# Front_left_lamp_v1.net
KiCad netlist of a schematic drawn in EAGLE
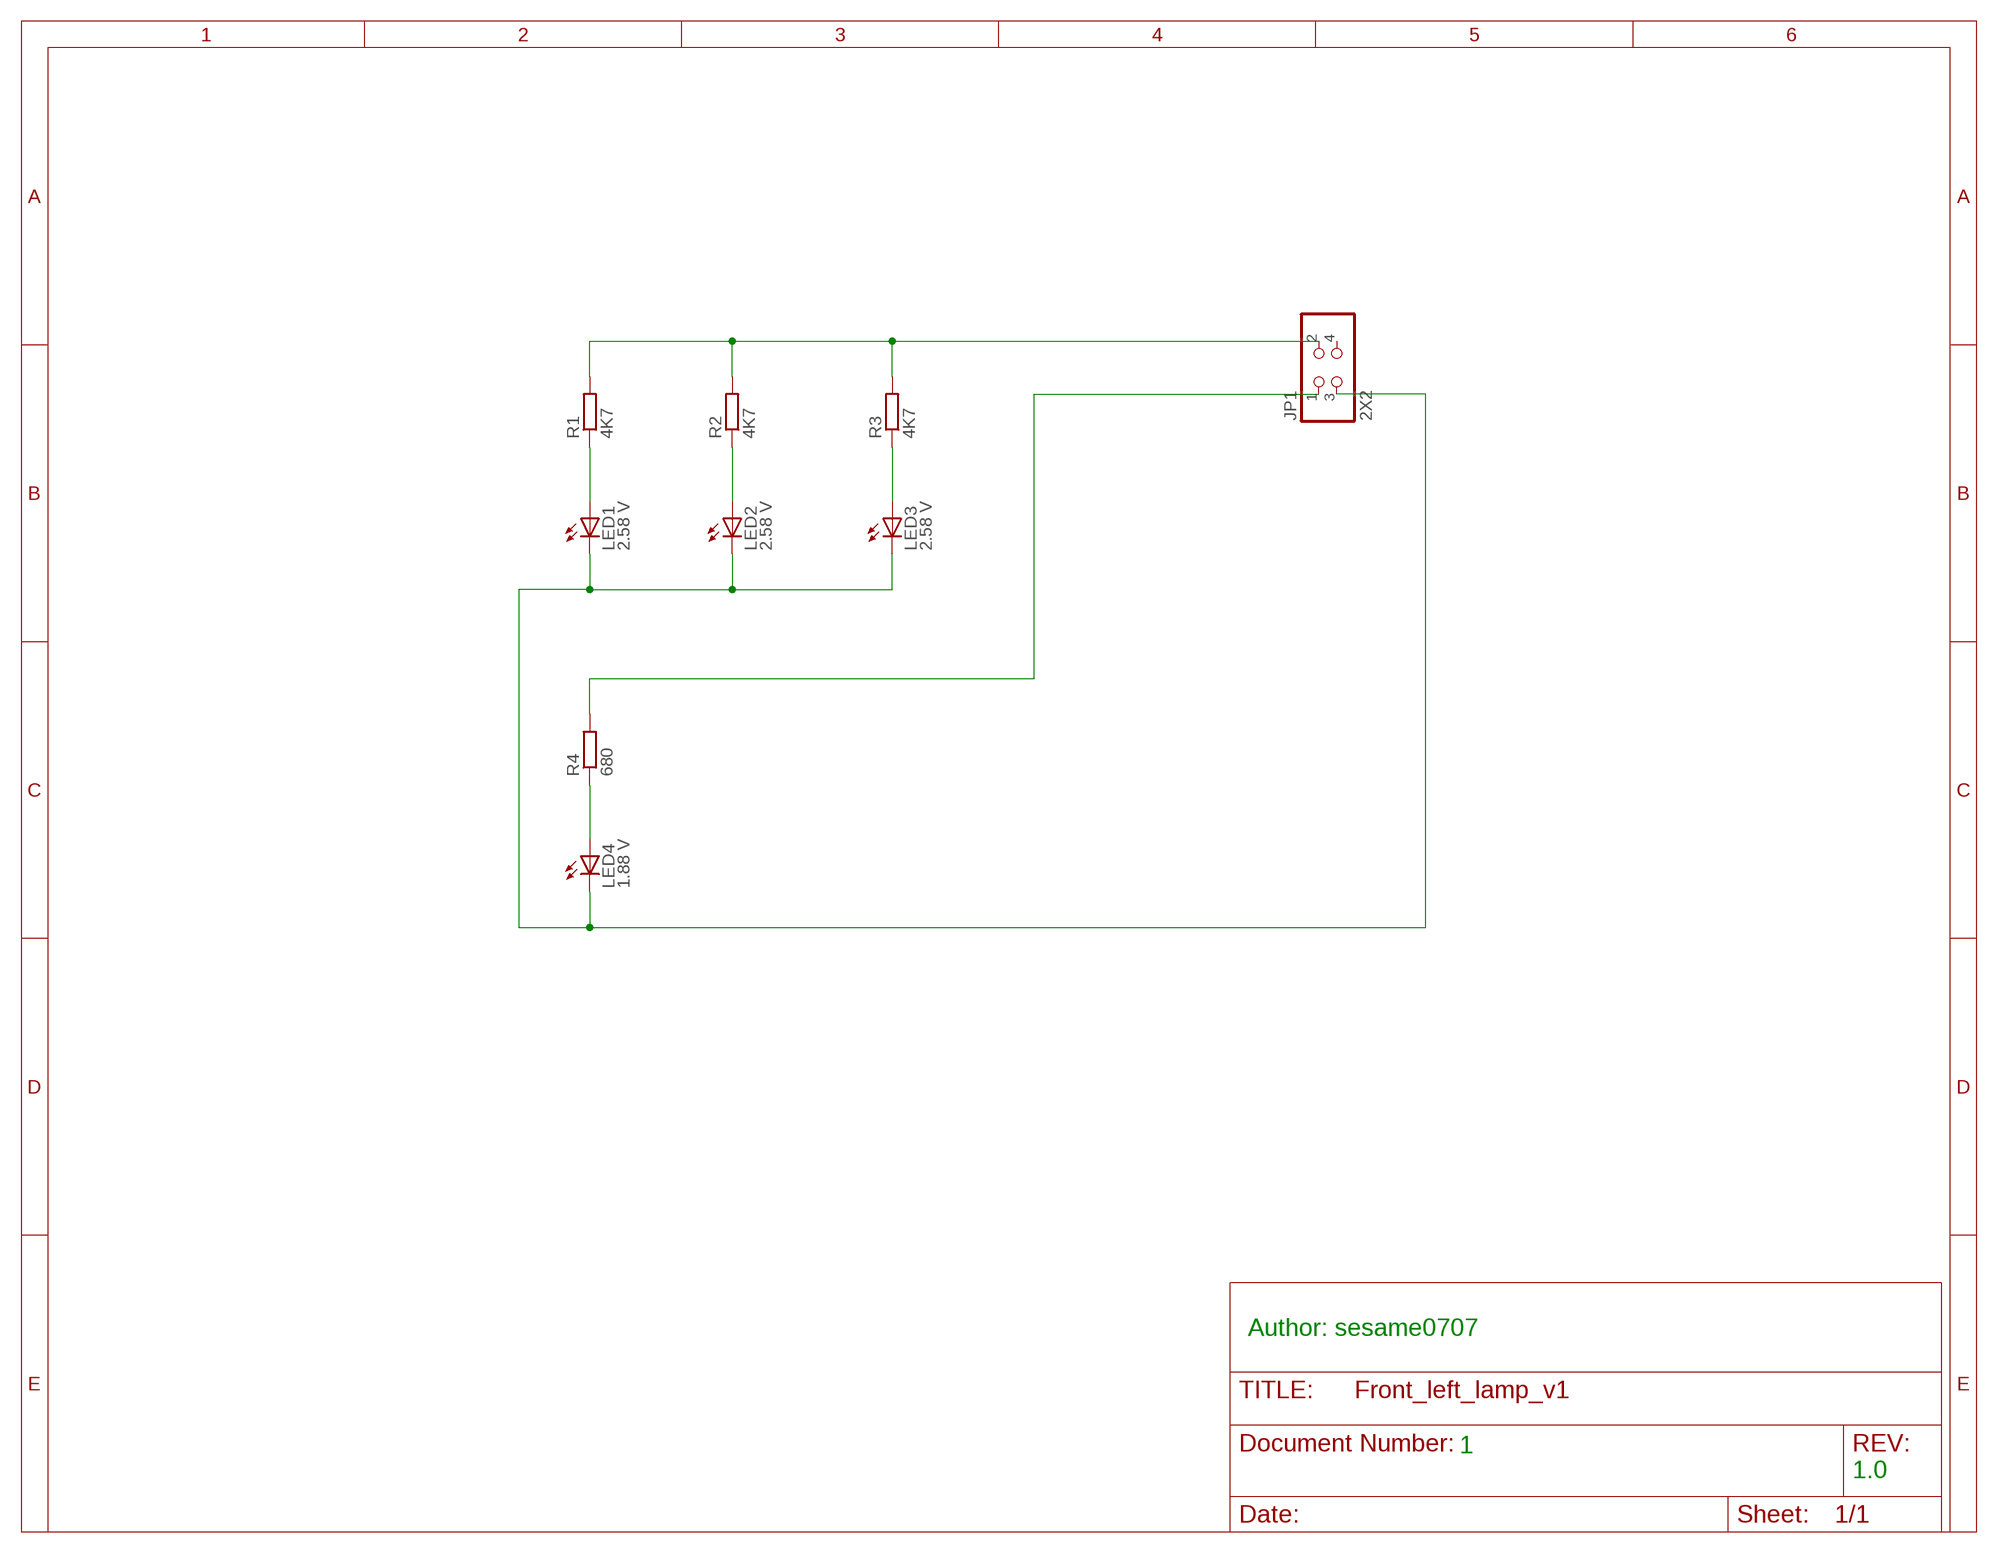
[diagram p0: schematic, sheet 1]

(export (version "E")
  (design (tool "Eeschema 10.0.6"))
  (components
    (comp (ref "JP1")
      (value "2X2")
      (footprint "eagle-import:2X02")
      (libsource (lib "eagle-import") (part "PINHD-2X2"))
    )
    (comp (ref "LED1")
      (value "2.58 V")
      (footprint "eagle-import:LED5MM")
      (libsource (lib "eagle-import") (part "LED5MM"))
    )
    (comp (ref "LED2")
      (value "2.58 V")
      (footprint "eagle-import:LED5MM")
      (libsource (lib "eagle-import") (part "LED5MM"))
    )
    (comp (ref "LED3")
      (value "2.58 V")
      (footprint "eagle-import:LED5MM")
      (libsource (lib "eagle-import") (part "LED5MM"))
    )
    (comp (ref "LED4")
      (value "1.88 V")
      (footprint "eagle-import:LED5MM")
      (libsource (lib "eagle-import") (part "LED5MM"))
    )
    (comp (ref "R1")
      (value "4K7")
      (footprint "eagle-import:0204V")
      (libsource (lib "eagle-import") (part "R-EU_0204/2V"))
    )
    (comp (ref "R2")
      (value "4K7")
      (footprint "eagle-import:0204V")
      (libsource (lib "eagle-import") (part "R-EU_0204/2V"))
    )
    (comp (ref "R3")
      (value "4K7")
      (footprint "eagle-import:0204V")
      (libsource (lib "eagle-import") (part "R-EU_0204/2V"))
    )
    (comp (ref "R4")
      (value "680")
      (footprint "eagle-import:0204V")
      (libsource (lib "eagle-import") (part "R-EU_0204/2V"))
    )
  )
  (nets
    (net (code "1") (name "Net-(JP1-Pad1)") (class "Default")
      (node (ref "JP1") (pin "1") (pinfunction "1_1") (pintype "passive"))
      (node (ref "R4") (pin "2") (pinfunction "2_2") (pintype "passive"))
    )
    (net (code "2") (name "Net-(JP1-Pad2)") (class "Default")
      (node (ref "JP1") (pin "2") (pinfunction "2_2") (pintype "passive"))
      (node (ref "R1") (pin "2") (pinfunction "2_2") (pintype "passive"))
      (node (ref "R2") (pin "2") (pinfunction "2_2") (pintype "passive"))
      (node (ref "R3") (pin "2") (pinfunction "2_2") (pintype "passive"))
    )
    (net (code "3") (name "Net-(LED1-C)") (class "Default")
      (node (ref "JP1") (pin "3") (pinfunction "3_3") (pintype "passive"))
      (node (ref "LED1") (pin "K") (pinfunction "C_K") (pintype "passive"))
      (node (ref "LED2") (pin "K") (pinfunction "C_K") (pintype "passive"))
      (node (ref "LED3") (pin "K") (pinfunction "C_K") (pintype "passive"))
      (node (ref "LED4") (pin "K") (pinfunction "C_K") (pintype "passive"))
    )
    (net (code "4") (name "Net-(LED1-PadA)") (class "Default")
      (node (ref "LED1") (pin "A") (pinfunction "A_A") (pintype "passive"))
      (node (ref "R1") (pin "1") (pinfunction "1_1") (pintype "passive"))
    )
    (net (code "5") (name "Net-(LED2-PadA)") (class "Default")
      (node (ref "LED2") (pin "A") (pinfunction "A_A") (pintype "passive"))
      (node (ref "R2") (pin "1") (pinfunction "1_1") (pintype "passive"))
    )
    (net (code "6") (name "Net-(LED3-PadA)") (class "Default")
      (node (ref "LED3") (pin "A") (pinfunction "A_A") (pintype "passive"))
      (node (ref "R3") (pin "1") (pinfunction "1_1") (pintype "passive"))
    )
    (net (code "7") (name "Net-(LED4-PadA)") (class "Default")
      (node (ref "LED4") (pin "A") (pinfunction "A_A") (pintype "passive"))
      (node (ref "R4") (pin "1") (pinfunction "1_1") (pintype "passive"))
    )
    (net (code "8") (name "unconnected-(JP1-Pad4)") (class "Default")
      (node (ref "JP1") (pin "4") (pinfunction "4_4") (pintype "passive"))
    )
  )
)
